# POWER_Management.net
KiCad netlist of a schematic drawn in Altium Designer
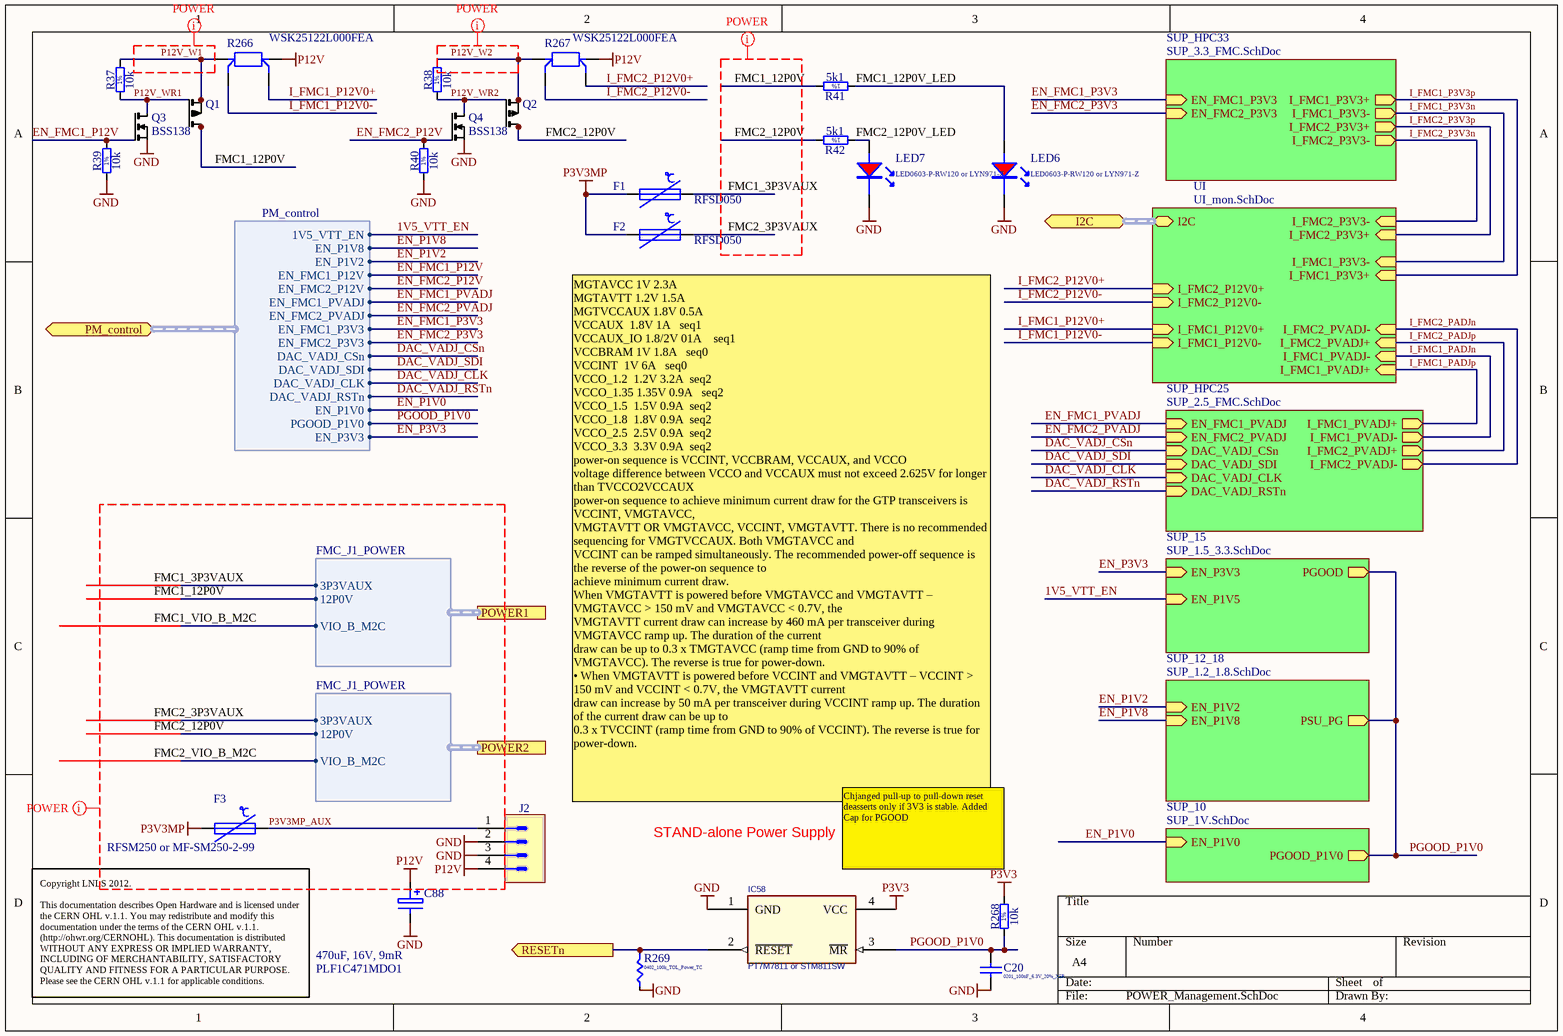
[diagram p0: POWER_Management.SchDoc]

(export (version "E")
  (design (tool "Eeschema 10.0.6"))
  (components
    (comp (ref "C20")
      (value "0201_100nF_6.3V_20%_X5R")
      (footprint "CAPC0603X33N")
      (fields (field (name "PART NUMBER") "Ceramic_0201"))
      (libsource (lib "Capacitors") (part "Capacitor"))
    )
    (comp (ref "C88")
      (value "PLF1C471MDO1")
      (footprint "CAPPR500-1000X1250")
      (description "POLY, 470uF, 16V, ESR: 9mR")
      (fields (field (name "ALTIUM_VALUE") "470uF, 16V, 9mR"))
      (libsource (lib "LIBRARY_SCH") (part "CAP_POLYMER_10mm"))
    )
    (comp (ref "F1")
      (value "RFSD050")
      (footprint "PTC_SMD_1812")
      (description "0.50A/15V")
      (libsource (lib "LIBRARY_SCH") (part "F_PTC_1812"))
    )
    (comp (ref "F2")
      (value "RFSD050")
      (footprint "PTC_SMD_1812")
      (description "0.50A/15V")
      (libsource (lib "LIBRARY_SCH") (part "F_PTC_1812"))
    )
    (comp (ref "F3")
      (value "RFSM250 or MF-SM250-2-99")
      (footprint "SMD150-2")
      (description "2.50A/15V")
      (libsource (lib "LIBRARY_SCH") (part "F_PTC_9.5x6mm"))
    )
    (comp (ref "IC58")
      (value "PT7M7811 or STM811SW")
      (footprint "SOT143B")
      (description "voltage supervisor")
      (libsource (lib "LIBRARY_SCH") (part "VOLT_STM811"))
    )
    (comp (ref "J2")
      (value "Mini-Fit Jr.™")
      (footprint "MOLEX_39-28-1043")
      (description "Connector 4 Male")
      (fields
        (field (name "PART NUMBER") "MOLEX_39-28-1043")
        (field (name "MANUFACTURER") "MOLEX")
        (field (name "AUTHOR") "CERN DEM JLC")
      )
      (libsource (lib "Connectors") (part "Connector 4 Male"))
    )
    (comp (ref "LED6")
      (value "LED0603-P-RW120 or LYN971-Z")
      (footprint "led_0603R")
      (description "LED 0603 red")
      (libsource (lib "LIBRARY_SCH") (part "LED_0603R"))
    )
    (comp (ref "LED7")
      (value "LED0603-P-RW120 or LYN971-Z")
      (footprint "led_0603R")
      (description "LED 0603 red")
      (libsource (lib "LIBRARY_SCH") (part "LED_0603R"))
    )
    (comp (ref "Q1")
      (value "IRF9317PBF  or IRF9310PbF")
      (footprint "so-8")
      (description "PMOS 30V, 4.6mR, 20A, 2.5W")
      (libsource (lib "LIBRARY_SCH") (part "Q_IRF9310"))
    )
    (comp (ref "Q2")
      (value "IRF9317PBF  or IRF9310PbF")
      (footprint "so-8")
      (description "PMOS 30V, 4.6mR, 20A, 2.5W")
      (libsource (lib "LIBRARY_SCH") (part "Q_IRF9310"))
    )
    (comp (ref "Q3")
      (value "BSS138")
      (footprint "SOT95P251X112-3N")
      (libsource (lib "LIBRARY_SCH") (part "Q_BSS138"))
    )
    (comp (ref "Q4")
      (value "BSS138")
      (footprint "SOT95P251X112-3N")
      (libsource (lib "LIBRARY_SCH") (part "Q_BSS138"))
    )
    (comp (ref "R37")
      (value "10k")
      (footprint "0402R")
      (description "Resistor - 1%")
      (fields
        (field (name "PART NUMBER") "R0603_10K_1%_0.1W_100PPM")
        (field (name "POWER") "0.1W")
        (field (name "AUTHOR") "CERN DEM JLC")
      )
      (libsource (lib "Resistors") (part "Resistor - 1%"))
    )
    (comp (ref "R38")
      (value "10k")
      (footprint "0402R")
      (description "Resistor - 1%")
      (fields
        (field (name "PART NUMBER") "R0603_10K_1%_0.1W_100PPM")
        (field (name "POWER") "0.1W")
        (field (name "AUTHOR") "CERN DEM JLC")
      )
      (libsource (lib "Resistors") (part "Resistor - 1%"))
    )
    (comp (ref "R39")
      (value "10k")
      (footprint "0402R")
      (description "Resistor - 1%")
      (fields
        (field (name "PART NUMBER") "R0603_10K_1%_0.1W_100PPM")
        (field (name "POWER") "0.1W")
        (field (name "AUTHOR") "CERN DEM JLC")
      )
      (libsource (lib "Resistors") (part "Resistor - 1%"))
    )
    (comp (ref "R40")
      (value "10k")
      (footprint "0402R")
      (description "Resistor - 1%")
      (fields
        (field (name "PART NUMBER") "R0603_10K_1%_0.1W_100PPM")
        (field (name "POWER") "0.1W")
        (field (name "AUTHOR") "CERN DEM JLC")
      )
      (libsource (lib "Resistors") (part "Resistor - 1%"))
    )
    (comp (ref "R41")
      (value "5k1")
      (footprint "0603R")
      (description "Resistor - 1%")
      (fields
        (field (name "PART NUMBER") "R0603_5K1_1%_0.1W_100PPM")
        (field (name "POWER") "0.1W")
        (field (name "AUTHOR") "CERN DEM JLC")
      )
      (libsource (lib "Resistors") (part "Resistor - 1%"))
    )
    (comp (ref "R42")
      (value "5k1")
      (footprint "0603R")
      (description "Resistor - 1%")
      (fields
        (field (name "PART NUMBER") "R0603_5K1_1%_0.1W_100PPM")
        (field (name "POWER") "0.1W")
        (field (name "AUTHOR") "CERN DEM JLC")
      )
      (libsource (lib "Resistors") (part "Resistor - 1%"))
    )
    (comp (ref "R266")
      (value "WSK25122L000FEA")
      (footprint "RES_WSK2512")
      (description "RESISTOR, METAL STRIP, 0.001 OHM 1%")
      (libsource (lib "LIBRARY_SCH") (part "RES_POW_Kelvin"))
    )
    (comp (ref "R267")
      (value "WSK25122L000FEA")
      (footprint "RES_WSK2512")
      (description "RESISTOR, METAL STRIP, 0.001 OHM 1%")
      (libsource (lib "LIBRARY_SCH") (part "RES_POW_Kelvin"))
    )
    (comp (ref "R268")
      (value "10k")
      (footprint "0402R")
      (description "Resistor - 1%")
      (fields
        (field (name "PART NUMBER") "R0603_10K_1%_0.1W_100PPM")
        (field (name "POWER") "0.1W")
        (field (name "AUTHOR") "CERN DEM JLC")
      )
      (libsource (lib "Resistors") (part "Resistor - 1%"))
    )
    (comp (ref "R269")
      (value "0402_100k_TOL_Power_TC")
      (footprint "RESC1005X40N")
      (fields (field (name "PART NUMBER") "SMT_0402"))
      (libsource (lib "Resistors") (part "Resistor"))
    )
  )
  (nets
    (net (code "10") (name "/EN_FMC1_P12V") (class "Default")
      (node (ref "Q3") (pin "1") (pinfunction "G_1") (pintype "input"))
      (node (ref "R39") (pin "2") (pinfunction "2_2") (pintype "passive"))
    )
    (net (code "13") (name "/EN_FMC2_P12V") (class "Default")
      (node (ref "Q4") (pin "1") (pinfunction "G_1") (pintype "input"))
      (node (ref "R40") (pin "2") (pinfunction "2_2") (pintype "passive"))
    )
    (net (code "19") (name "/FMC1_3P3VAUX") (class "Default")
      (node (ref "F1") (pin "2") (pinfunction "2_2") (pintype "passive"))
    )
    (net (code "20") (name "/FMC1_12P0V") (class "Default")
      (node (ref "Q1") (pin "5") (pinfunction "D1_5") (pintype "open_collector"))
      (node (ref "Q1") (pin "6") (pinfunction "D1_6") (pintype "open_collector"))
      (node (ref "Q1") (pin "7") (pinfunction "D1_7") (pintype "open_collector"))
      (node (ref "Q1") (pin "8") (pinfunction "D1_8") (pintype "open_collector"))
      (node (ref "R41") (pin "2") (pinfunction "2_2") (pintype "passive"))
    )
    (net (code "21") (name "/FMC1_12P0V_LED") (class "Default")
      (node (ref "LED6") (pin "A") (pinfunction "A_A") (pintype "passive"))
      (node (ref "R41") (pin "1") (pinfunction "1_1") (pintype "passive"))
    )
    (net (code "23") (name "/FMC2_3P3VAUX") (class "Default")
      (node (ref "F2") (pin "2") (pinfunction "2_2") (pintype "passive"))
    )
    (net (code "24") (name "/FMC2_12P0V") (class "Default")
      (node (ref "Q2") (pin "5") (pinfunction "D1_5") (pintype "open_collector"))
      (node (ref "Q2") (pin "6") (pinfunction "D1_6") (pintype "open_collector"))
      (node (ref "Q2") (pin "7") (pinfunction "D1_7") (pintype "open_collector"))
      (node (ref "Q2") (pin "8") (pinfunction "D1_8") (pintype "open_collector"))
      (node (ref "R42") (pin "2") (pinfunction "2_2") (pintype "passive"))
    )
    (net (code "25") (name "/FMC2_12P0V_LED") (class "Default")
      (node (ref "LED7") (pin "A") (pinfunction "A_A") (pintype "passive"))
      (node (ref "R42") (pin "1") (pinfunction "1_1") (pintype "passive"))
    )
    (net (code "30") (name "/I_FMC1_P12V0+") (class "Default")
      (node (ref "R266") (pin "2a") (pinfunction "2a_2a") (pintype "passive"))
    )
    (net (code "31") (name "/I_FMC1_P12V0-") (class "Default")
      (node (ref "R266") (pin "1a") (pinfunction "1a_1a") (pintype "passive"))
    )
    (net (code "36") (name "/I_FMC2_P12V0+") (class "Default")
      (node (ref "R267") (pin "2a") (pinfunction "2a_2a") (pintype "passive"))
    )
    (net (code "37") (name "/I_FMC2_P12V0-") (class "Default")
      (node (ref "R267") (pin "1a") (pinfunction "1a_1a") (pintype "passive"))
    )
    (net (code "40") (name "/P3V3MP_AUX") (class "Default")
      (node (ref "F3") (pin "2") (pinfunction "2_2") (pintype "passive"))
      (node (ref "J2") (pin "1") (pinfunction "1_1") (pintype "passive"))
    )
    (net (code "41") (name "/P12V_W1") (class "Default")
      (node (ref "Q1") (pin "1") (pinfunction "S1_1") (pintype "open_emitter"))
      (node (ref "Q1") (pin "2") (pinfunction "S1_2") (pintype "open_emitter"))
      (node (ref "Q1") (pin "3") (pinfunction "S1_3") (pintype "open_emitter"))
      (node (ref "R266") (pin "1") (pinfunction "1_1") (pintype "passive"))
      (node (ref "R37") (pin "2") (pinfunction "2_2") (pintype "passive"))
    )
    (net (code "42") (name "/P12V_W2") (class "Default")
      (node (ref "Q2") (pin "1") (pinfunction "S1_1") (pintype "open_emitter"))
      (node (ref "Q2") (pin "2") (pinfunction "S1_2") (pintype "open_emitter"))
      (node (ref "Q2") (pin "3") (pinfunction "S1_3") (pintype "open_emitter"))
      (node (ref "R267") (pin "1") (pinfunction "1_1") (pintype "passive"))
      (node (ref "R38") (pin "2") (pinfunction "2_2") (pintype "passive"))
    )
    (net (code "43") (name "/P12V_WR1") (class "Default")
      (node (ref "Q1") (pin "4") (pinfunction "G1_4") (pintype "input"))
      (node (ref "Q3") (pin "3") (pinfunction "D_3") (pintype "passive"))
      (node (ref "R37") (pin "1") (pinfunction "1_1") (pintype "passive"))
    )
    (net (code "44") (name "/P12V_WR2") (class "Default")
      (node (ref "Q2") (pin "4") (pinfunction "G1_4") (pintype "input"))
      (node (ref "Q4") (pin "3") (pinfunction "D_3") (pintype "passive"))
      (node (ref "R38") (pin "1") (pinfunction "1_1") (pintype "passive"))
    )
    (net (code "45") (name "/PGOOD_P1V0") (class "Default")
      (node (ref "C20") (pin "1") (pinfunction "1_1") (pintype "passive"))
      (node (ref "IC58") (pin "3") (pinfunction "~{MR}_3") (pintype "input"))
      (node (ref "R268") (pin "1") (pinfunction "1_1") (pintype "passive"))
    )
    (net (code "46") (name "/RESETn") (class "Default")
      (node (ref "IC58") (pin "2") (pinfunction "~{RESET}_2") (pintype "output"))
      (node (ref "R269") (pin "1") (pinfunction "+_1") (pintype "passive"))
    )
    (net (code "49") (name "GND") (class "Default")
      (node (ref "C20") (pin "2") (pinfunction "2_2") (pintype "passive"))
      (node (ref "C88") (pin "2") (pinfunction "2_2") (pintype "passive"))
      (node (ref "IC58") (pin "1") (pinfunction "GND_1") (pintype "power_in"))
      (node (ref "J2") (pin "2") (pinfunction "2_2") (pintype "passive"))
      (node (ref "J2") (pin "3") (pinfunction "3_3") (pintype "passive"))
      (node (ref "LED6") (pin "K") (pinfunction "K_K") (pintype "passive"))
      (node (ref "LED7") (pin "K") (pinfunction "K_K") (pintype "passive"))
      (node (ref "Q3") (pin "2") (pinfunction "S_2") (pintype "passive"))
      (node (ref "Q4") (pin "2") (pinfunction "S_2") (pintype "passive"))
      (node (ref "R269") (pin "2") (pinfunction "-_2") (pintype "passive"))
      (node (ref "R39") (pin "1") (pinfunction "1_1") (pintype "passive"))
      (node (ref "R40") (pin "1") (pinfunction "1_1") (pintype "passive"))
    )
    (net (code "50") (name "P3V3") (class "Default")
      (node (ref "IC58") (pin "4") (pinfunction "VCC_4") (pintype "power_in"))
      (node (ref "R268") (pin "2") (pinfunction "2_2") (pintype "passive"))
    )
    (net (code "51") (name "P3V3MP") (class "Default")
      (node (ref "F1") (pin "1") (pinfunction "1_1") (pintype "passive"))
      (node (ref "F2") (pin "1") (pinfunction "1_1") (pintype "passive"))
      (node (ref "F3") (pin "1") (pinfunction "1_1") (pintype "passive"))
    )
    (net (code "52") (name "P12V") (class "Default")
      (node (ref "C88") (pin "1") (pinfunction "1_1") (pintype "passive"))
      (node (ref "J2") (pin "4") (pinfunction "4_4") (pintype "passive"))
      (node (ref "R266") (pin "2") (pinfunction "2_2") (pintype "passive"))
      (node (ref "R267") (pin "2") (pinfunction "2_2") (pintype "passive"))
    )
  )
)
